# tail_light.net
KiCad netlist of a schematic drawn in EAGLE
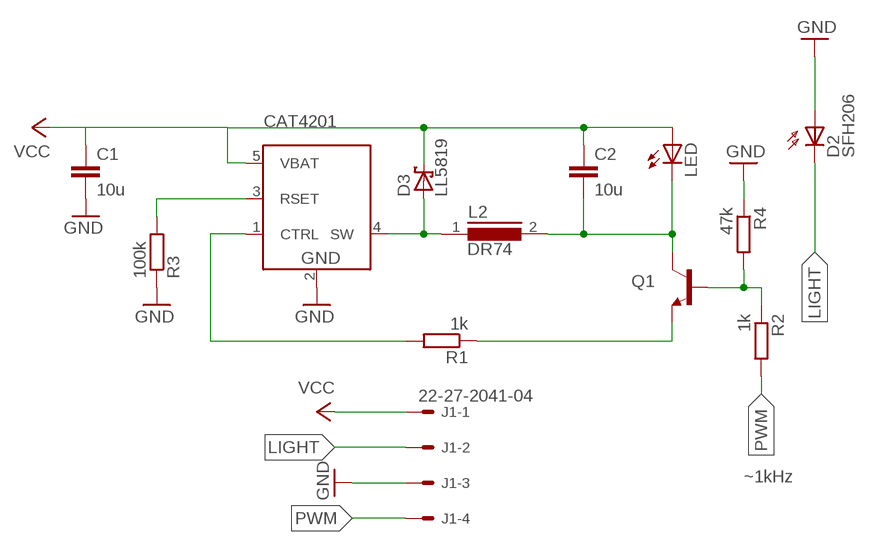
[diagram p0: schematic, sheet 1]

(export (version "E")
  (design (tool "Eeschema 10.0.6"))
  (components
    (comp (ref "C1")
      (value "10u")
      (footprint "eagle-import:C0805")
      (libsource (lib "eagle-import") (part "C-EUC0805"))
    )
    (comp (ref "C2")
      (value "10u")
      (footprint "eagle-import:C0805")
      (libsource (lib "eagle-import") (part "C-EUC0805"))
    )
    (comp (ref "CAT4201")
      (value "CAT4201TF")
      (footprint "eagle-import:SOT23-DBV")
      (libsource (lib "eagle-import") (part "CAT4201TF"))
    )
    (comp (ref "D2")
      (value "SFH206")
      (footprint "eagle-import:SFH206")
      (fields (field (name "MPN") "SFH206K"))
      (libsource (lib "eagle-import") (part "SFH206"))
    )
    (comp (ref "D3")
      (value "LL5819")
      (footprint "eagle-import:MELF-MLL41")
      (libsource (lib "eagle-import") (part "DIODESCHOTTKY"))
    )
    (comp (ref "J1")
      (value "22-27-2041-04")
      (footprint "eagle-import:6410-04")
      (libsource (lib "eagle-import") (part "22-?-0427-2041"))
    )
    (comp (ref "L2")
      (value "DR74")
      (footprint "eagle-import:DR74")
      (libsource (lib "eagle-import") (part "DR74"))
    )
    (comp (ref "LED")
      (value "LEDMINI-TOP")
      (footprint "eagle-import:OSRAM-MINI-TOP-LED")
      (libsource (lib "eagle-import") (part "LEDMINI-TOP"))
    )
    (comp (ref "Q1")
      (value "TRANSISTOR_NPNSOT23-3")
      (footprint "eagle-import:SOT23-3")
      (libsource (lib "eagle-import") (part "TRANSISTOR_NPNSOT23-3"))
    )
    (comp (ref "R1")
      (value "1k")
      (footprint "eagle-import:R1206")
      (libsource (lib "eagle-import") (part "resistor_R-EU_R1206"))
    )
    (comp (ref "R2")
      (value "1k")
      (footprint "eagle-import:R1206")
      (libsource (lib "eagle-import") (part "resistor_R-EU_R1206"))
    )
    (comp (ref "R3")
      (value "100k")
      (footprint "eagle-import:R1206")
      (libsource (lib "eagle-import") (part "R-EU_R1206"))
    )
    (comp (ref "R4")
      (value "47k")
      (footprint "eagle-import:R1206")
      (libsource (lib "eagle-import") (part "resistor_R-EU_R1206"))
    )
  )
  (nets
    (net (code "1") (name "GND") (class "Default")
      (node (ref "C1") (pin "2") (pinfunction "2_2") (pintype "passive"))
      (node (ref "CAT4201") (pin "2") (pinfunction "GND_2") (pintype "bidirectional"))
      (node (ref "D2") (pin "A") (pinfunction "A_A") (pintype "passive"))
      (node (ref "J1") (pin "3") (pinfunction "S_3") (pintype "passive"))
      (node (ref "R3") (pin "1") (pinfunction "1_1") (pintype "passive"))
      (node (ref "R4") (pin "1") (pinfunction "1_1") (pintype "passive"))
    )
    (net (code "2") (name "LIGHT") (class "Default")
      (node (ref "D2") (pin "K") (pinfunction "C_K") (pintype "passive"))
      (node (ref "J1") (pin "2") (pinfunction "S_2") (pintype "passive"))
    )
    (net (code "3") (name "Net-(CAT4201-CTRL)") (class "Default")
      (node (ref "CAT4201") (pin "1") (pinfunction "CTRL_1") (pintype "bidirectional"))
      (node (ref "R1") (pin "2") (pinfunction "2_2") (pintype "passive"))
    )
    (net (code "4") (name "Net-(CAT4201-RSET)") (class "Default")
      (node (ref "CAT4201") (pin "3") (pinfunction "RSET_3") (pintype "bidirectional"))
      (node (ref "R3") (pin "2") (pinfunction "2_2") (pintype "passive"))
    )
    (net (code "5") (name "Net-(CAT4201-SW)") (class "Default")
      (node (ref "CAT4201") (pin "4") (pinfunction "SW_4") (pintype "bidirectional"))
      (node (ref "D3") (pin "A") (pinfunction "A_A") (pintype "passive"))
      (node (ref "L2") (pin "1") (pinfunction "1_1") (pintype "passive"))
    )
    (net (code "6") (name "Net-(Q1-B)") (class "Default")
      (node (ref "Q1") (pin "1") (pinfunction "B_1") (pintype "passive"))
      (node (ref "R2") (pin "1") (pinfunction "1_1") (pintype "passive"))
      (node (ref "R4") (pin "2") (pinfunction "2_2") (pintype "passive"))
    )
    (net (code "7") (name "Net-(Q1-C)") (class "Default")
      (node (ref "C2") (pin "2") (pinfunction "2_2") (pintype "passive"))
      (node (ref "L2") (pin "2") (pinfunction "2_2") (pintype "passive"))
      (node (ref "LED") (pin "C") (pinfunction "C_C") (pintype "passive"))
      (node (ref "Q1") (pin "3") (pinfunction "C_3") (pintype "passive"))
    )
    (net (code "8") (name "Net-(Q1-E)") (class "Default")
      (node (ref "Q1") (pin "2") (pinfunction "E_2") (pintype "passive"))
      (node (ref "R1") (pin "1") (pinfunction "1_1") (pintype "passive"))
    )
    (net (code "9") (name "PWM") (class "Default")
      (node (ref "J1") (pin "4") (pinfunction "S_4") (pintype "passive"))
      (node (ref "R2") (pin "2") (pinfunction "2_2") (pintype "passive"))
    )
    (net (code "10") (name "VCC") (class "Default")
      (node (ref "C1") (pin "1") (pinfunction "1_1") (pintype "passive"))
      (node (ref "C2") (pin "1") (pinfunction "1_1") (pintype "passive"))
      (node (ref "CAT4201") (pin "5") (pinfunction "VBAT_5") (pintype "bidirectional"))
      (node (ref "D3") (pin "C") (pinfunction "C_C") (pintype "passive"))
      (node (ref "J1") (pin "1") (pinfunction "S_1") (pintype "passive"))
      (node (ref "LED") (pin "A") (pinfunction "A_A") (pintype "passive"))
    )
  )
)
